# TEMP_SENSORS.net
KiCad netlist of a schematic drawn in Altium Designer
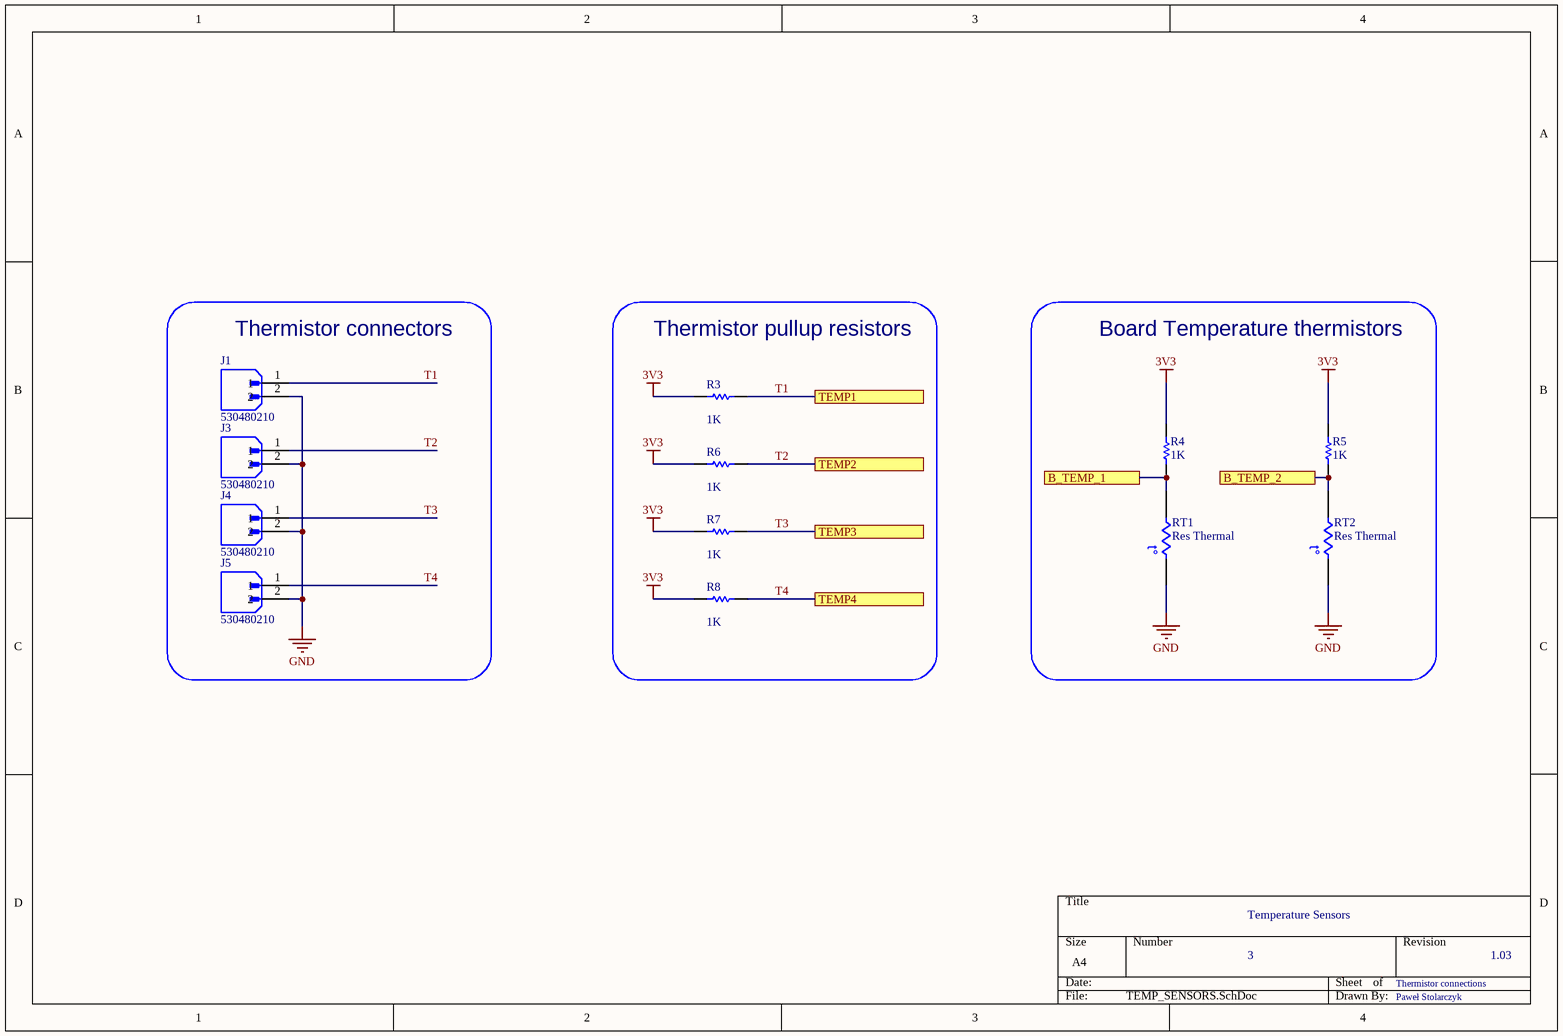
[diagram p0: TEMP_SENSORS.SchDoc]

(export (version "E")
  (design (tool "Eeschema 10.0.6"))
  (components
    (comp (ref "J1")
      (value "530480210")
      (footprint "MOLEX_530480210")
      (description "Conn Shrouded Header (4 Sides) HDR 2 POS 1.25mm Solder RA Side Entry Thru-Hole PicoBladeâ„¢ Tray")
      (fields (field (name "MF") "Molex"))
      (libsource (lib "530480210") (part "530480210"))
    )
    (comp (ref "J3")
      (value "530480210")
      (footprint "MOLEX_530480210")
      (description "Conn Shrouded Header (4 Sides) HDR 2 POS 1.25mm Solder RA Side Entry Thru-Hole PicoBladeâ„¢ Tray")
      (fields (field (name "MF") "Molex"))
      (libsource (lib "530480210") (part "530480210"))
    )
    (comp (ref "J4")
      (value "530480210")
      (footprint "MOLEX_530480210")
      (description "Conn Shrouded Header (4 Sides) HDR 2 POS 1.25mm Solder RA Side Entry Thru-Hole PicoBladeâ„¢ Tray")
      (fields (field (name "MF") "Molex"))
      (libsource (lib "530480210") (part "530480210"))
    )
    (comp (ref "J5")
      (value "530480210")
      (footprint "MOLEX_530480210")
      (description "Conn Shrouded Header (4 Sides) HDR 2 POS 1.25mm Solder RA Side Entry Thru-Hole PicoBladeâ„¢ Tray")
      (fields (field (name "MF") "Molex"))
      (libsource (lib "530480210") (part "530480210"))
    )
    (comp (ref "R3")
      (value "1K")
      (footprint "0402")
      (description "Resistor")
      (fields (field (name "Comment") "Res1") (field (name "PUBLISHER") "Altium Limited"))
      (libsource (lib "Miscellaneous Devices") (part "Res1"))
    )
    (comp (ref "R4")
      (value "1K")
      (footprint "0402")
      (description "Resistor")
      (fields (field (name "Comment") "Res1") (field (name "PUBLISHER") "Altium Limited"))
      (libsource (lib "Miscellaneous Devices") (part "Res1"))
    )
    (comp (ref "R5")
      (value "1K")
      (footprint "0402")
      (description "Resistor")
      (fields (field (name "Comment") "Res1") (field (name "PUBLISHER") "Altium Limited"))
      (libsource (lib "Miscellaneous Devices") (part "Res1"))
    )
    (comp (ref "R6")
      (value "1K")
      (footprint "0402")
      (description "Resistor")
      (fields (field (name "Comment") "Res1") (field (name "PUBLISHER") "Altium Limited"))
      (libsource (lib "Miscellaneous Devices") (part "Res1"))
    )
    (comp (ref "R7")
      (value "1K")
      (footprint "0402")
      (description "Resistor")
      (fields (field (name "Comment") "Res1") (field (name "PUBLISHER") "Altium Limited"))
      (libsource (lib "Miscellaneous Devices") (part "Res1"))
    )
    (comp (ref "R8")
      (value "1K")
      (footprint "0402")
      (description "Resistor")
      (fields (field (name "Comment") "Res1") (field (name "PUBLISHER") "Altium Limited"))
      (libsource (lib "Miscellaneous Devices") (part "Res1"))
    )
    (comp (ref "RT1")
      (value "Res Thermal")
      (footprint "0402")
      (description "Thermistor")
      (fields (field (name "PUBLISHER") "Altium Limited"))
      (libsource (lib "Miscellaneous Devices") (part "Res Thermal"))
    )
    (comp (ref "RT2")
      (value "Res Thermal")
      (footprint "0402")
      (description "Thermistor")
      (fields (field (name "PUBLISHER") "Altium Limited"))
      (libsource (lib "Miscellaneous Devices") (part "Res Thermal"))
    )
  )
  (nets
    (net (code "1") (name "/B_TEMP_1") (class "Default")
      (node (ref "R4") (pin "1") (pinfunction "1_1") (pintype "passive"))
      (node (ref "RT1") (pin "2") (pinfunction "2_2") (pintype "passive"))
    )
    (net (code "2") (name "/B_TEMP_2") (class "Default")
      (node (ref "R5") (pin "1") (pinfunction "1_1") (pintype "passive"))
      (node (ref "RT2") (pin "2") (pinfunction "2_2") (pintype "passive"))
    )
    (net (code "3") (name "/T1") (class "Default")
      (node (ref "J1") (pin "1") (pinfunction "1_1") (pintype "passive"))
      (node (ref "R3") (pin "1") (pinfunction "1_1") (pintype "passive"))
    )
    (net (code "4") (name "/T2") (class "Default")
      (node (ref "J3") (pin "1") (pinfunction "1_1") (pintype "passive"))
      (node (ref "R6") (pin "1") (pinfunction "1_1") (pintype "passive"))
    )
    (net (code "5") (name "/T3") (class "Default")
      (node (ref "J4") (pin "1") (pinfunction "1_1") (pintype "passive"))
      (node (ref "R7") (pin "1") (pinfunction "1_1") (pintype "passive"))
    )
    (net (code "6") (name "/T4") (class "Default")
      (node (ref "J5") (pin "1") (pinfunction "1_1") (pintype "passive"))
      (node (ref "R8") (pin "1") (pinfunction "1_1") (pintype "passive"))
    )
    (net (code "7") (name "3V3") (class "Default")
      (node (ref "R3") (pin "2") (pinfunction "2_2") (pintype "passive"))
      (node (ref "R4") (pin "2") (pinfunction "2_2") (pintype "passive"))
      (node (ref "R5") (pin "2") (pinfunction "2_2") (pintype "passive"))
      (node (ref "R6") (pin "2") (pinfunction "2_2") (pintype "passive"))
      (node (ref "R7") (pin "2") (pinfunction "2_2") (pintype "passive"))
      (node (ref "R8") (pin "2") (pinfunction "2_2") (pintype "passive"))
    )
    (net (code "8") (name "GND") (class "Default")
      (node (ref "J1") (pin "2") (pinfunction "2_2") (pintype "passive"))
      (node (ref "J3") (pin "2") (pinfunction "2_2") (pintype "passive"))
      (node (ref "J4") (pin "2") (pinfunction "2_2") (pintype "passive"))
      (node (ref "J5") (pin "2") (pinfunction "2_2") (pintype "passive"))
      (node (ref "RT1") (pin "1") (pinfunction "1_1") (pintype "passive"))
      (node (ref "RT2") (pin "1") (pinfunction "1_1") (pintype "passive"))
    )
  )
)
